# 5R_Supply_doc.net
KiCad netlist of a schematic drawn in Altium Designer
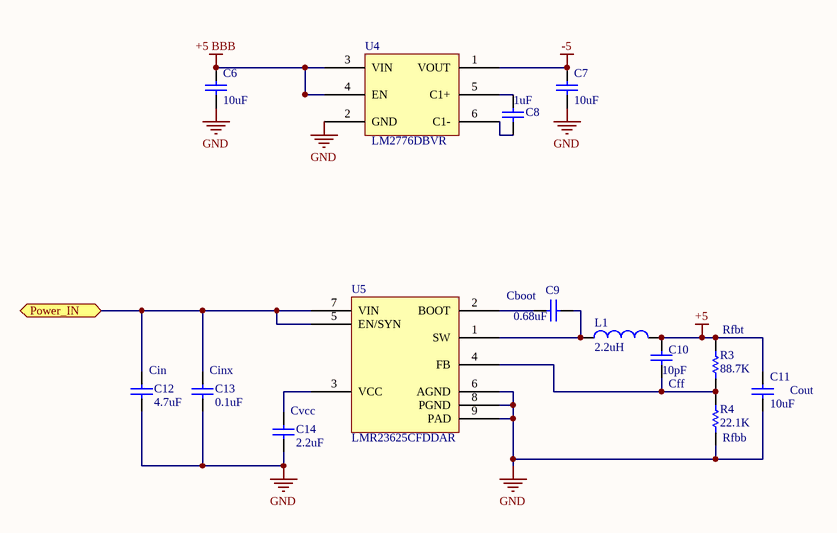
[diagram p0: 5R_Supply.doc.SchDoc]

(export (version "E")
  (design (tool "Eeschema 10.0.6"))
  (components
    (comp (ref "C6")
      (value "10uF")
      (footprint "CAPC0805(2012)145_N")
      (description "CAP CER 10UF 16V X6S 0805")
      (fields
        (field (name "MANUFACTURER") "TDK Corporation")
        (field (name "MANUFACTURER PART NUMBER") "C2012X6S1C106K085AC")
      )
      (libsource (lib "Altium Content Vault") (part "CMP-1036-04795-1"))
    )
    (comp (ref "C7")
      (value "10uF")
      (footprint "CAPC0805(2012)145_N")
      (description "CAP CER 10UF 16V X6S 0805")
      (fields
        (field (name "MANUFACTURER") "TDK Corporation")
        (field (name "MANUFACTURER PART NUMBER") "C2012X6S1C106K085AC")
      )
      (libsource (lib "Altium Content Vault") (part "CMP-1036-04795-1"))
    )
    (comp (ref "C8")
      (value "1uF")
      (footprint "CAPC0805(2012)145_N")
      (description "CAP CER 1UF 25V X7R 0805")
      (fields
        (field (name "MANUFACTURER") "Yageo")
        (field (name "MANUFACTURER PART NUMBER") "CC0805KKX7R6BB105")
      )
      (libsource (lib "Altium Content Vault") (part "CMP-1036-04795-1"))
    )
    (comp (ref "C9")
      (value "0.68uF")
      (footprint "1608[0603]")
      (description "CAP CER 0.68UF 50V X5R 0603")
      (fields
        (field (name "MANUFACTURER") "TDK Corporation")
        (field (name "MANUFACTURER PART NUMBER") "C1608X5R1H684K080AB")
      )
      (libsource (lib "Miscellaneous Devices") (part "Cap Semi"))
    )
    (comp (ref "C10")
      (value "10pF")
      (footprint "CAPC0805(2012)145_N")
      (description "CAP CER 10PF 16V C0G/NP0 0805")
      (fields
        (field (name "MANUFACTURER") "KEMET")
        (field (name "MANUFACTURER PART NUMBER") "C0805C100M4GACTU")
      )
      (libsource (lib "Altium Content Vault") (part "CMP-1036-04795-1"))
    )
    (comp (ref "C11")
      (value "10uF")
      (footprint "CAPC0805(2012)145_N")
      (description "CAP CER 10UF 16V X6S 0805")
      (fields
        (field (name "MANUFACTURER") "TDK Corporation")
        (field (name "MANUFACTURER PART NUMBER") "C2012X6S1C106K085AC")
      )
      (libsource (lib "Altium Content Vault") (part "CMP-1036-04795-1"))
    )
    (comp (ref "C12")
      (value "4.7uF")
      (footprint "C1210")
      (description "CAP CER 4.7UF 50V X7R 1210")
      (fields
        (field (name "MANUFACTURER") "Murata Electronics North America")
        (field (name "MANUFACTURER PART NUMBER") "GRM32ER71H475KA88L")
        (field (name "PUBLISHER") "Altium Limited")
      )
      (libsource (lib "Miscellaneous Devices") (part "Cap Semi"))
    )
    (comp (ref "C13")
      (value "0.1uF")
      (footprint "1608[0603]")
      (description "CAP CER 0.1UF 50V X5R 0603")
      (fields
        (field (name "MANUFACTURER") "TDK Corporation")
        (field (name "MANUFACTURER PART NUMBER") "C1608X5R1H104K080AA")
      )
      (libsource (lib "Miscellaneous Devices") (part "Cap Semi"))
    )
    (comp (ref "C14")
      (value "2.2uF")
      (footprint "1608[0603]")
      (description "CAP CER 2.2UF 10V X7R 0603")
      (libsource (lib "Miscellaneous Devices") (part "Cap Semi"))
    )
    (comp (ref "L1")
      (value "2.2uH")
      (footprint "PA4332")
      (description "FIXED IND 2.2UH 4.3A 48 MOHM SMD")
      (fields
        (field (name "MANUFACTURER") "Pulse Electronics Power")
        (field (name "MANUFACTURER PART NUMBER") "PA4332.222NLT")
      )
      (libsource (lib "Miscellaneous Devices") (part "Inductor"))
    )
    (comp (ref "R3")
      (value "88.7K")
      (footprint "RESC0805(2012)_M")
      (description "RES SMD 88.7K OHM 1% 1/8W 0805")
      (fields
        (field (name "MANUFACTURER") "Vishay Dale")
        (field (name "MANUFACTURER PART NUMBER") "CRCW080588K7FKEA")
      )
      (libsource (lib "Altium Content Vault") (part "CMP-1013-00017-1"))
    )
    (comp (ref "R4")
      (value "22.1K")
      (footprint "RESC0805(2012)_M")
      (description "RES SMD 22.1K OHM 1% 1/8W 0805")
      (fields
        (field (name "MANUFACTURER") "Vishay Dale")
        (field (name "MANUFACTURER PART NUMBER") "CRCW080522K1FKEA")
      )
      (libsource (lib "Altium Content Vault") (part "CMP-1013-00017-1"))
    )
    (comp (ref "U4")
      (value "LM2776DBVR")
      (footprint "LM2776DBVR")
      (description "IC REG SWTCHD CAP INV 6SOT23")
      (fields (field (name "MANUFACTURER") "Texas Instruments"))
      (libsource (lib "ZLS_Schematic_lib") (part "LM2776DBVR"))
    )
    (comp (ref "U5")
      (value "LMR23625CFDDAR")
      (footprint "LMR23625CDDAR")
      (description "IC REG BUCK ADJ 2.5A SYNC 8SOPWR")
      (fields (field (name "MANUFACTURER") "Texas Instruments"))
      (libsource (lib "ZLS_Schematic_lib") (part "LMR23625CDDAR"))
    )
  )
  (nets
    (net (code "1") (name "+5") (class "Default")
      (node (ref "C10") (pin "1") (pinfunction "1_1") (pintype "passive"))
      (node (ref "C11") (pin "1") (pinfunction "1_1") (pintype "passive"))
      (node (ref "L1") (pin "2") (pinfunction "2_2") (pintype "passive"))
      (node (ref "R3") (pin "2") (pinfunction "2_2") (pintype "passive"))
    )
    (net (code "2") (name "+5 BBB") (class "Default")
      (node (ref "C6") (pin "1") (pinfunction "1_1") (pintype "passive"))
      (node (ref "U4") (pin "3") (pinfunction "VIN_3") (pintype "passive"))
      (node (ref "U4") (pin "4") (pinfunction "EN_4") (pintype "passive"))
    )
    (net (code "3") (name "-5") (class "Default")
      (node (ref "C7") (pin "1") (pinfunction "1_1") (pintype "passive"))
      (node (ref "U4") (pin "1") (pinfunction "VOUT_1") (pintype "passive"))
    )
    (net (code "4") (name "/Power_IN") (class "Default")
      (node (ref "C12") (pin "2") (pinfunction "2_2") (pintype "passive"))
      (node (ref "C13") (pin "2") (pinfunction "2_2") (pintype "passive"))
      (node (ref "U5") (pin "5") (pinfunction "EN/SYN_5") (pintype "passive"))
      (node (ref "U5") (pin "7") (pinfunction "VIN_7") (pintype "passive"))
    )
    (net (code "5") (name "GND") (class "Default")
      (node (ref "C11") (pin "2") (pinfunction "2_2") (pintype "passive"))
      (node (ref "C12") (pin "1") (pinfunction "1_1") (pintype "passive"))
      (node (ref "C13") (pin "1") (pinfunction "1_1") (pintype "passive"))
      (node (ref "C14") (pin "1") (pinfunction "1_1") (pintype "passive"))
      (node (ref "C6") (pin "2") (pinfunction "2_2") (pintype "passive"))
      (node (ref "C7") (pin "2") (pinfunction "2_2") (pintype "passive"))
      (node (ref "R4") (pin "1") (pinfunction "1_1") (pintype "passive"))
      (node (ref "U4") (pin "2") (pinfunction "GND_2") (pintype "passive"))
      (node (ref "U5") (pin "6") (pinfunction "AGND_6") (pintype "passive"))
      (node (ref "U5") (pin "8") (pinfunction "PGND_8") (pintype "passive"))
      (node (ref "U5") (pin "9") (pinfunction "PAD_9") (pintype "passive"))
    )
    (net (code "6") (name "Net-(U4-C1+)") (class "Default")
      (node (ref "C8") (pin "1") (pinfunction "1_1") (pintype "passive"))
      (node (ref "U4") (pin "5") (pinfunction "C1+_5") (pintype "passive"))
    )
    (net (code "7") (name "Net-(U4-C1-)") (class "Default")
      (node (ref "C8") (pin "2") (pinfunction "2_2") (pintype "passive"))
      (node (ref "U4") (pin "6") (pinfunction "C1-_6") (pintype "passive"))
    )
    (net (code "8") (name "Net-(U5-BOOT)") (class "Default")
      (node (ref "C9") (pin "1") (pinfunction "1_1") (pintype "passive"))
      (node (ref "U5") (pin "2") (pinfunction "BOOT_2") (pintype "passive"))
    )
    (net (code "9") (name "Net-(U5-FB)") (class "Default")
      (node (ref "C10") (pin "2") (pinfunction "2_2") (pintype "passive"))
      (node (ref "R3") (pin "1") (pinfunction "1_1") (pintype "passive"))
      (node (ref "R4") (pin "2") (pinfunction "2_2") (pintype "passive"))
      (node (ref "U5") (pin "4") (pinfunction "FB_4") (pintype "passive"))
    )
    (net (code "10") (name "Net-(U5-SW)") (class "Default")
      (node (ref "C9") (pin "2") (pinfunction "2_2") (pintype "passive"))
      (node (ref "L1") (pin "1") (pinfunction "1_1") (pintype "passive"))
      (node (ref "U5") (pin "1") (pinfunction "SW_1") (pintype "passive"))
    )
    (net (code "11") (name "Net-(U5-VCC)") (class "Default")
      (node (ref "C14") (pin "2") (pinfunction "2_2") (pintype "passive"))
      (node (ref "U5") (pin "3") (pinfunction "VCC_3") (pintype "passive"))
    )
  )
)
